# FMU_Power_FMU3_REV_G.net
KiCad netlist of a schematic drawn in Altium Designer
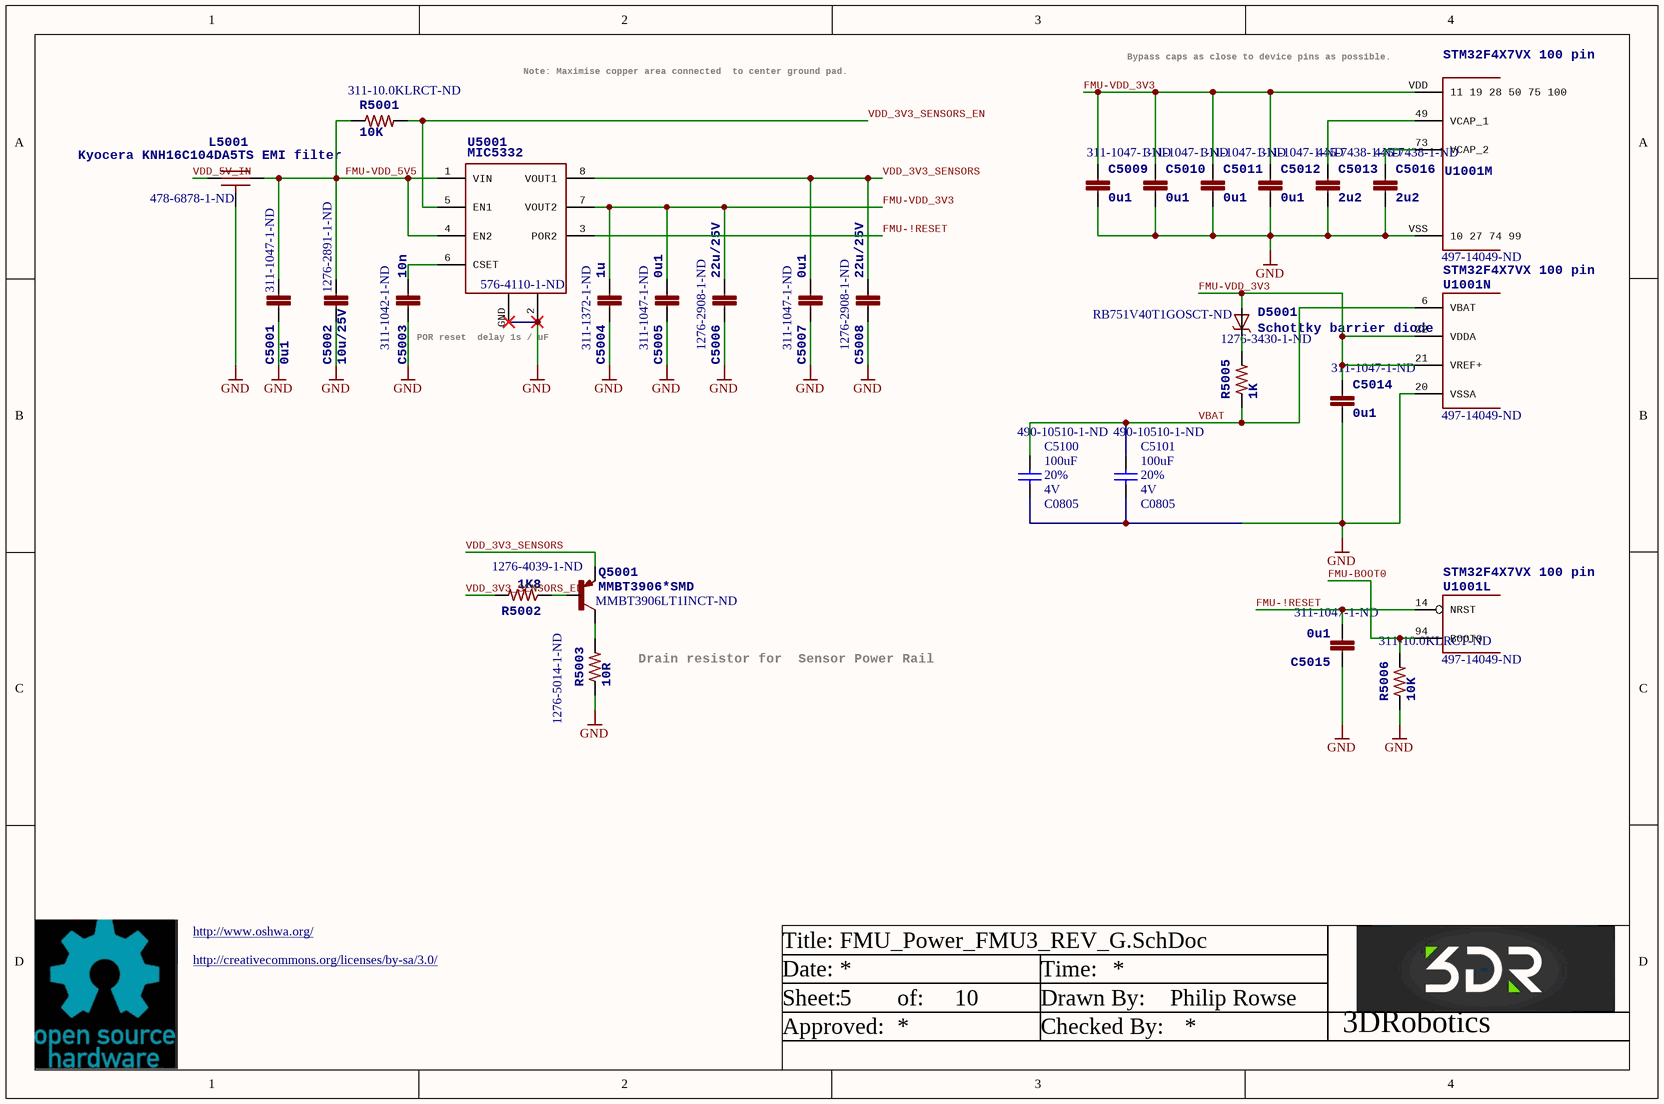
[diagram p0: FMU_Power_FMU3_REV_G.SchDoc]

(export (version "E")
  (design (tool "Eeschema 10.0.6"))
  (components
    (comp (ref "C5001")
      (value "0u1")
      (footprint "0402-CAP")
      (description "CAP CER 0.1UF 16V Y5V 0402")
      (fields
        (field (name "PARTNO") "CC0402ZRY5V7BB104")
        (field (name "SUPPLIER PART NUMBER 1") "311-1047-1-ND")
        (field (name "3DR_PARTNO") "ECM0700")
      )
      (libsource (lib "pixhawk2") (part "CAP0402"))
    )
    (comp (ref "C5002")
      (value "10u/25V")
      (footprint "0805-CAP")
      (description "CAP CER 10UF 25V 10% X5R 0805")
      (fields
        (field (name "PARTNO") "CL21A106KAYNNNE")
        (field (name "SUPPLIER PART NUMBER 1") "1276-2891-1-ND")
        (field (name "3DR_PARTNO") "ECM0714")
      )
      (libsource (lib "pixhawk2") (part "CAP0805"))
    )
    (comp (ref "C5003")
      (value "10n")
      (footprint "0402-CAP")
      (description "CAP CER 10000PF 16V 10% X7R 0402")
      (fields
        (field (name "PARTNO") "CC0402KRX7R7BB103")
        (field (name "SUPPLIER PART NUMBER 1") "311-1042-1-ND")
        (field (name "3DR_PARTNO") "ECM0711")
      )
      (libsource (lib "") (part "CAP0402_1"))
    )
    (comp (ref "C5004")
      (value "1u")
      (footprint "0603-CAP")
      (description "CAP CER 1UF 16V Y5V 0603")
      (fields
        (field (name "PARTNO") "CC0603ZRY5V7BB105")
        (field (name "SUPPLIER PART NUMBER 1") "311-1372-1-ND")
        (field (name "3DR_PARTNO") "ECM0705")
      )
      (libsource (lib "pixhawk2") (part "CAP0603"))
    )
    (comp (ref "C5005")
      (value "0u1")
      (footprint "0402-CAP")
      (description "CAP CER 0.1UF 16V Y5V 0402")
      (fields
        (field (name "PARTNO") "CC0402ZRY5V7BB104")
        (field (name "SUPPLIER PART NUMBER 1") "311-1047-1-ND")
        (field (name "3DR_PARTNO") "ECM0700")
      )
      (libsource (lib "pixhawk2") (part "CAP0402"))
    )
    (comp (ref "C5006")
      (value "22u/25V")
      (footprint "0805-CAP")
      (description "CAP CER 22UF 25V 20% X5R 0805")
      (fields
        (field (name "PARTNO") "CL21A226MAQNNNE")
        (field (name "SUPPLIER PART NUMBER 1") "1276-2908-1-ND")
        (field (name "3DR_PARTNO") "ECM0715")
      )
      (libsource (lib "pixhawk2") (part "CAP0805"))
    )
    (comp (ref "C5007")
      (value "0u1")
      (footprint "0402-CAP")
      (description "CAP CER 0.1UF 16V Y5V 0402")
      (fields
        (field (name "PARTNO") "CC0402ZRY5V7BB104")
        (field (name "SUPPLIER PART NUMBER 1") "311-1047-1-ND")
        (field (name "3DR_PARTNO") "ECM0700")
      )
      (libsource (lib "pixhawk2") (part "CAP0402"))
    )
    (comp (ref "C5008")
      (value "22u/25V")
      (footprint "0805-CAP")
      (description "CAP CER 22UF 25V 20% X5R 0805")
      (fields
        (field (name "PARTNO") "CL21A226MAQNNNE")
        (field (name "SUPPLIER PART NUMBER 1") "1276-2908-1-ND")
        (field (name "3DR_PARTNO") "ECM0715")
      )
      (libsource (lib "pixhawk2") (part "CAP0805"))
    )
    (comp (ref "C5009")
      (value "0u1")
      (footprint "0402-CAP")
      (description "CAP CER 0.1UF 16V Y5V 0402")
      (fields
        (field (name "PARTNO") "CC0402ZRY5V7BB104")
        (field (name "SUPPLIER PART NUMBER 1") "311-1047-1-ND")
        (field (name "3DR_PARTNO") "ECM0700")
      )
      (libsource (lib "pixhawk2") (part "CAP0402"))
    )
    (comp (ref "C5010")
      (value "0u1")
      (footprint "0402-CAP")
      (description "CAP CER 0.1UF 16V Y5V 0402")
      (fields
        (field (name "PARTNO") "CC0402ZRY5V7BB104")
        (field (name "SUPPLIER PART NUMBER 1") "311-1047-1-ND")
        (field (name "3DR_PARTNO") "ECM0700")
      )
      (libsource (lib "pixhawk2") (part "CAP0402"))
    )
    (comp (ref "C5011")
      (value "0u1")
      (footprint "0402-CAP")
      (description "CAP CER 0.1UF 16V Y5V 0402")
      (fields
        (field (name "PARTNO") "CC0402ZRY5V7BB104")
        (field (name "SUPPLIER PART NUMBER 1") "311-1047-1-ND")
        (field (name "3DR_PARTNO") "ECM0700")
      )
      (libsource (lib "pixhawk2") (part "CAP0402"))
    )
    (comp (ref "C5012")
      (value "0u1")
      (footprint "0402-CAP")
      (description "CAP CER 0.1UF 16V Y5V 0402")
      (fields
        (field (name "PARTNO") "CC0402ZRY5V7BB104")
        (field (name "SUPPLIER PART NUMBER 1") "311-1047-1-ND")
        (field (name "3DR_PARTNO") "ECM0700")
      )
      (libsource (lib "pixhawk2") (part "CAP0402"))
    )
    (comp (ref "C5013")
      (value "2u2")
      (footprint "0603-CAP")
      (description "CAP CER 2.2UF 16V 10% X6S 0603")
      (fields
        (field (name "PARTNO") "C1608X6S1C225K080AC")
        (field (name "SUPPLIER PART NUMBER 1") "445-7438-1-ND")
        (field (name "3DR_PARTNO") "ECM0619")
      )
      (libsource (lib "pixhawk2") (part "CAP0603"))
    )
    (comp (ref "C5014")
      (value "0u1")
      (footprint "0402-CAP")
      (description "CAP CER 0.1UF 16V Y5V 0402")
      (fields
        (field (name "PARTNO") "CC0402ZRY5V7BB104")
        (field (name "SUPPLIER PART NUMBER 1") "311-1047-1-ND")
        (field (name "3DR_PARTNO") "ECM0700")
      )
      (libsource (lib "pixhawk2") (part "CAP0402"))
    )
    (comp (ref "C5015")
      (value "0u1")
      (footprint "0402-CAP")
      (description "CAP CER 0.1UF 16V Y5V 0402")
      (fields
        (field (name "PARTNO") "CC0402ZRY5V7BB104")
        (field (name "SUPPLIER PART NUMBER 1") "311-1047-1-ND")
        (field (name "3DR_PARTNO") "ECM0700")
      )
      (libsource (lib "") (part "CAP0402_2"))
    )
    (comp (ref "C5016")
      (value "2u2")
      (footprint "0603-CAP")
      (description "CAP CER 2.2UF 16V 10% X6S 0603")
      (fields
        (field (name "PARTNO") "C1608X6S1C225K080AC")
        (field (name "SUPPLIER PART NUMBER 1") "445-7438-1-ND")
        (field (name "3DR_PARTNO") "ECM0619")
      )
      (libsource (lib "pixhawk2") (part "CAP0603"))
    )
    (comp (ref "C5100")
      (value "100uF")
      (footprint "C0805")
      (fields
        (field (name "TOLERANCE") "20%")
        (field (name "VOLTAGE") "4V")
        (field (name "SUPPLIER PART NUMBER 1") "490-10510-1-ND")
        (field (name "Comment") "GRM21BR60G107ME15L")
      )
      (libsource (lib "3DR") (part "Capacitor"))
    )
    (comp (ref "C5101")
      (value "100uF")
      (footprint "C0805")
      (fields
        (field (name "TOLERANCE") "20%")
        (field (name "VOLTAGE") "4V")
        (field (name "SUPPLIER PART NUMBER 1") "490-10510-1-ND")
        (field (name "Comment") "GRM21BR60G107ME15L")
      )
      (libsource (lib "3DR") (part "Capacitor"))
    )
    (comp (ref "D5001")
      (value "Schottky barrier diode")
      (footprint "SOD323")
      (description "DIODE SCHOTTKY 30V 0.03A SOD323")
      (fields
        (field (name "SUPPLIER PART NUMBER 1") "RB751V40T1GOSCT-ND")
        (field (name "3DR_PARTNO") "ECM0839")
        (field (name "PARTNO") "RB751V40T1G")
      )
      (libsource (lib "pixhawk2") (part "DIODE-SCHOTTKY_SOD323"))
    )
    (comp (ref "L5001")
      (value "Kyocera KNH16C104DA5TS EMI filter")
      (footprint "KYOCERA-KNH16-DA")
      (description "FILTER CAP 0.1UF 2A 25V 0603")
      (fields
        (field (name "SUPPLIER PART NUMBER 1") "478-6878-1-ND")
        (field (name "3DR_PARTNO") "ECM0719")
        (field (name "PARTNO") "KNH16C104DA5TS")
      )
      (libsource (lib "pixhawk2") (part "KNH16C104DA5TS"))
    )
    (comp (ref "Q5001")
      (value "MMBT3906*SMD")
      (footprint "SOT23-BEC")
      (description "TRANSISTOR SWITCHING PNP SOT-23")
      (fields
        (field (name "SUPPLIER PART NUMBER 1") "MMBT3906LT1INCT-ND")
        (field (name "3DR_PARTNO") "ECM0833")
        (field (name "PARTNO") "MMBT 3906 LT1")
      )
      (libsource (lib "transistor-pnp") (part "MMBT3906*SMD"))
    )
    (comp (ref "R5001")
      (value "10K")
      (footprint "0402-RES")
      (description "RES 10K OHM 1/16W 1% 0402 SMD")
      (fields
        (field (name "PARTNO") "RC0402FR-0710KL")
        (field (name "SUPPLIER PART NUMBER 1") "311-10.0KLRCT-ND")
        (field (name "3DR_PARTNO") "ECM0800")
      )
      (libsource (lib "pixhawk2") (part "RESISTOR0402-RES"))
    )
    (comp (ref "R5002")
      (value "1K8")
      (footprint "0402-RES")
      (description "RES 1.8K OHM 1/16W 1% 0402")
      (fields
        (field (name "PARTNO") "RC1005F182CS")
        (field (name "SUPPLIER PART NUMBER 1") "1276-4039-1-ND")
        (field (name "3DR_PARTNO") "ECM0807")
      )
      (libsource (lib "pixhawk2") (part "RESISTOR0402-RES"))
    )
    (comp (ref "R5003")
      (value "10R")
      (footprint "0603-RES")
      (description "RES 10 OHM 1/10W 5% 0603")
      (fields
        (field (name "PARTNO") "RC1608J100CS")
        (field (name "SUPPLIER PART NUMBER 1") "1276-5014-1-ND")
        (field (name "3DR_PARTNO") "ECM0811")
      )
      (libsource (lib "pixhawk2") (part "RESISTOR0603-RES"))
    )
    (comp (ref "R5005")
      (value "1K")
      (footprint "0402-RES")
      (description "RES 1K OHM 1/16W 1% 0402")
      (fields
        (field (name "PARTNO") "RC1005F102CS")
        (field (name "SUPPLIER PART NUMBER 1") "1276-3430-1-ND")
        (field (name "3DR_PARTNO") "ECM0804")
      )
      (libsource (lib "pixhawk2") (part "RESISTOR0402-RES"))
    )
    (comp (ref "R5006")
      (value "10K")
      (footprint "0402-RES")
      (description "RES 10K OHM 1/16W 1% 0402 SMD")
      (fields
        (field (name "PARTNO") "RC0402FR-0710KL")
        (field (name "SUPPLIER PART NUMBER 1") "311-10.0KLRCT-ND")
        (field (name "3DR_PARTNO") "ECM0800")
      )
      (libsource (lib "pixhawk2") (part "RESISTOR0402-RES"))
    )
    (comp (ref "U1001")
      (value "STM32F4X7VX 100 pin")
      (footprint "TQFP100")
      (description "REV 3 Silicon or later IC MCU ARM 2MB FLASH 100LQFP")
      (fields (field (name "SUPPLIER PART NUMBER 1") "497-14049-ND") (field (name "3DR_PARTNO") "ECM0841"))
      (libsource (lib "pixhawk2") (part "STM32F4X7VX"))
    )
    (comp (ref "U5001")
      (value "MIC5332")
      (footprint "MLF-8-EPAD")
      (description "IC REG LDO 3.3V 0.3A 8TMLF")
      (fields
        (field (name "SUPPLIER PART NUMBER 1") "576-4110-1-ND")
        (field (name "3DR_PARTNO") "ECM0832")
        (field (name "PARTNO") "MIC5332-SSYMT TR")
      )
      (libsource (lib "pixhawk2") (part "MIC5332"))
    )
  )
  (nets
    (net (code "1") (name "/FMU-!RESET") (class "Default")
      (node (ref "C5015") (pin "P$2") (pinfunction "2_P$2") (pintype "passive"))
      (node (ref "U1001") (pin "14") (pinfunction "NRST_14") (pintype "passive"))
      (node (ref "U5001") (pin "3") (pinfunction "POR2_3") (pintype "passive"))
    )
    (net (code "2") (name "/FMU-BOOT0") (class "Default")
      (node (ref "R5006") (pin "P$2") (pinfunction "2_P$2") (pintype "passive"))
      (node (ref "U1001") (pin "94") (pinfunction "BOOT0_94") (pintype "passive"))
    )
    (net (code "3") (name "/FMU-VDD_3V3") (class "Default")
      (node (ref "C5004") (pin "P$1") (pinfunction "1_P$1") (pintype "passive"))
      (node (ref "C5005") (pin "P$1") (pinfunction "1_P$1") (pintype "passive"))
      (node (ref "C5006") (pin "P$1") (pinfunction "1_P$1") (pintype "passive"))
      (node (ref "C5009") (pin "P$1") (pinfunction "1_P$1") (pintype "passive"))
      (node (ref "C5010") (pin "P$1") (pinfunction "1_P$1") (pintype "passive"))
      (node (ref "C5011") (pin "P$1") (pinfunction "1_P$1") (pintype "passive"))
      (node (ref "C5012") (pin "P$1") (pinfunction "1_P$1") (pintype "passive"))
      (node (ref "C5014") (pin "P$1") (pinfunction "1_P$1") (pintype "passive"))
      (node (ref "D5001") (pin "A") (pinfunction "A_A") (pintype "passive"))
      (node (ref "U1001") (pin "21") (pinfunction "VREF+_21") (pintype "passive"))
      (node (ref "U1001") (pin "22") (pinfunction "VDDA_22") (pintype "power_in"))
      (node (ref "U1001") (pin "VDD") (pinfunction "11_19_28_50_75_100_VDD") (pintype "power_in"))
      (node (ref "U5001") (pin "7") (pinfunction "VOUT2_7") (pintype "passive"))
    )
    (net (code "4") (name "/FMU-VDD_5V5") (class "Default")
      (node (ref "C5001") (pin "P$1") (pinfunction "1_P$1") (pintype "passive"))
      (node (ref "C5002") (pin "P$1") (pinfunction "1_P$1") (pintype "passive"))
      (node (ref "L5001") (pin "P$2") (pinfunction "P$2_P$2") (pintype "passive"))
      (node (ref "R5001") (pin "P$1") (pinfunction "1_P$1") (pintype "passive"))
      (node (ref "U5001") (pin "1") (pinfunction "VIN_1") (pintype "passive"))
      (node (ref "U5001") (pin "4") (pinfunction "EN2_4") (pintype "passive"))
    )
    (net (code "5") (name "/VBAT") (class "Default")
      (node (ref "C5100") (pin "2") (pinfunction "2_2") (pintype "passive"))
      (node (ref "C5101") (pin "2") (pinfunction "2_2") (pintype "passive"))
      (node (ref "R5005") (pin "P$1") (pinfunction "1_P$1") (pintype "passive"))
      (node (ref "U1001") (pin "6") (pinfunction "VBAT_6") (pintype "power_in"))
    )
    (net (code "6") (name "/VDD_3V3_SENSORS") (class "Default")
      (node (ref "C5007") (pin "P$1") (pinfunction "1_P$1") (pintype "passive"))
      (node (ref "C5008") (pin "P$1") (pinfunction "1_P$1") (pintype "passive"))
      (node (ref "Q5001") (pin "E") (pinfunction "E_E") (pintype "passive"))
      (node (ref "U5001") (pin "8") (pinfunction "VOUT1_8") (pintype "passive"))
    )
    (net (code "7") (name "/VDD_3V3_SENSORS_EN") (class "Default")
      (node (ref "R5001") (pin "P$2") (pinfunction "2_P$2") (pintype "passive"))
      (node (ref "R5002") (pin "P$2") (pinfunction "2_P$2") (pintype "passive"))
      (node (ref "U5001") (pin "5") (pinfunction "EN1_5") (pintype "passive"))
    )
    (net (code "8") (name "/VDD_5V_IN") (class "Default")
      (node (ref "L5001") (pin "P$1") (pinfunction "P$1_P$1") (pintype "passive"))
    )
    (net (code "9") (name "GND") (class "Default")
      (node (ref "C5001") (pin "P$2") (pinfunction "2_P$2") (pintype "passive"))
      (node (ref "C5002") (pin "P$2") (pinfunction "2_P$2") (pintype "passive"))
      (node (ref "C5003") (pin "P$1") (pinfunction "1_P$1") (pintype "passive"))
      (node (ref "C5004") (pin "P$2") (pinfunction "2_P$2") (pintype "passive"))
      (node (ref "C5005") (pin "P$2") (pinfunction "2_P$2") (pintype "passive"))
      (node (ref "C5006") (pin "P$2") (pinfunction "2_P$2") (pintype "passive"))
      (node (ref "C5007") (pin "P$2") (pinfunction "2_P$2") (pintype "passive"))
      (node (ref "C5008") (pin "P$2") (pinfunction "2_P$2") (pintype "passive"))
      (node (ref "C5009") (pin "P$2") (pinfunction "2_P$2") (pintype "passive"))
      (node (ref "C5010") (pin "P$2") (pinfunction "2_P$2") (pintype "passive"))
      (node (ref "C5011") (pin "P$2") (pinfunction "2_P$2") (pintype "passive"))
      (node (ref "C5012") (pin "P$2") (pinfunction "2_P$2") (pintype "passive"))
      (node (ref "C5013") (pin "P$2") (pinfunction "2_P$2") (pintype "passive"))
      (node (ref "C5014") (pin "P$2") (pinfunction "2_P$2") (pintype "passive"))
      (node (ref "C5015") (pin "P$1") (pinfunction "1_P$1") (pintype "passive"))
      (node (ref "C5016") (pin "P$2") (pinfunction "2_P$2") (pintype "passive"))
      (node (ref "C5100") (pin "1") (pinfunction "1_1") (pintype "passive"))
      (node (ref "C5101") (pin "1") (pinfunction "1_1") (pintype "passive"))
      (node (ref "L5001") (pin "GND") (pinfunction "GND_GND") (pintype "passive"))
      (node (ref "R5003") (pin "1") (pinfunction "1_1") (pintype "passive"))
      (node (ref "R5006") (pin "P$1") (pinfunction "1_P$1") (pintype "passive"))
      (node (ref "U1001") (pin "20") (pinfunction "VSSA_20") (pintype "power_in"))
      (node (ref "U1001") (pin "VSS") (pinfunction "10_27_74_99_VSS") (pintype "power_in"))
      (node (ref "U5001") (pin "2") (pinfunction "GND_2") (pintype "power_in"))
      (node (ref "U5001") (pin "GND") (pinfunction "GND_GND") (pintype "power_in"))
    )
    (net (code "10") (name "Net-(C5003-2)") (class "Default")
      (node (ref "C5003") (pin "P$2") (pinfunction "2_P$2") (pintype "passive"))
      (node (ref "U5001") (pin "6") (pinfunction "CSET_6") (pintype "passive"))
    )
    (net (code "11") (name "Net-(C5013-1)") (class "Default")
      (node (ref "C5013") (pin "P$1") (pinfunction "1_P$1") (pintype "passive"))
      (node (ref "U1001") (pin "49") (pinfunction "VCAP_1_49") (pintype "power_in"))
    )
    (net (code "12") (name "Net-(C5016-1)") (class "Default")
      (node (ref "C5016") (pin "P$1") (pinfunction "1_P$1") (pintype "passive"))
      (node (ref "U1001") (pin "73") (pinfunction "VCAP_2_73") (pintype "power_in"))
    )
    (net (code "13") (name "Net-(Q5001-PadC)") (class "Default")
      (node (ref "Q5001") (pin "C") (pinfunction "C_C") (pintype "passive"))
      (node (ref "R5003") (pin "2") (pinfunction "2_2") (pintype "passive"))
    )
    (net (code "14") (name "Net-(R5002-1)") (class "Default")
      (node (ref "Q5001") (pin "B") (pinfunction "B_B") (pintype "passive"))
      (node (ref "R5002") (pin "P$1") (pinfunction "1_P$1") (pintype "passive"))
    )
    (net (code "15") (name "Net-(R5005-2)") (class "Default")
      (node (ref "D5001") (pin "C") (pinfunction "C_C") (pintype "passive"))
      (node (ref "R5005") (pin "P$2") (pinfunction "2_P$2") (pintype "passive"))
    )
  )
)
